# Switch.net
KiCad netlist of a schematic drawn in Altium Designer
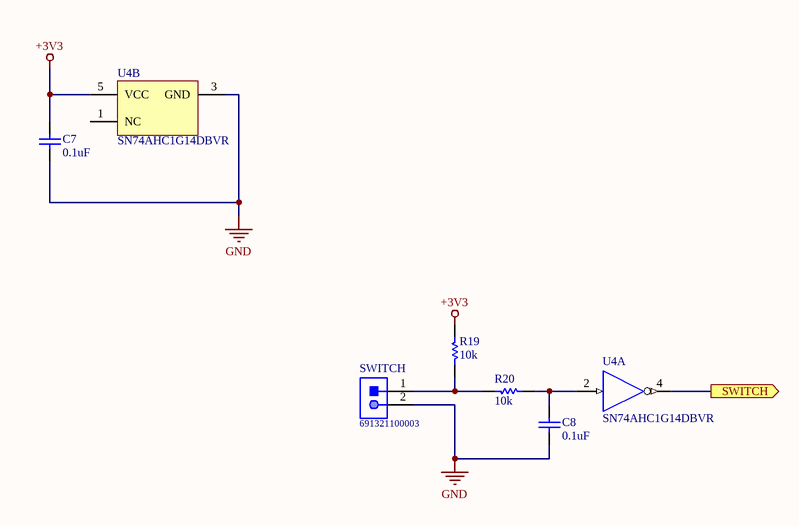
[diagram p0: Switch.SchDoc]

(export (version "E")
  (design (tool "Eeschema 10.0.6"))
  (components
    (comp (ref "C7")
      (value "0.1uF")
      (footprint "CAPC1608X87X35NL15T15")
      (fields (field (name "PART NUMBER") "C0603X104K5RACTU") (field (name "MANUFACTURER") "Kemet"))
      (libsource (lib "Altium Content Vault") (part "CAP"))
    )
    (comp (ref "C8")
      (value "0.1uF")
      (footprint "CAPC1608X87X35NL15T15")
      (fields (field (name "PART NUMBER") "C0603X104K5RACTU") (field (name "MANUFACTURER") "Kemet"))
      (libsource (lib "Altium Content Vault") (part "CAP"))
    )
    (comp (ref "R19")
      (value "10k")
      (footprint "RESC1609X55X30LL15T15")
      (description "Chip Resistor, 10 KOhm, +/- 1%, 0.1 W, -55 to 155 degC, 0603 (1608 Metric), RoHS, Tape and Reel")
      (fields (field (name "TOLERANCE") "1%") (field (name "MANUFACTURER") "Panasonic"))
      (libsource (lib "Altium Content Vault") (part "RES-2"))
    )
    (comp (ref "R20")
      (value "10k")
      (footprint "RESC1609X55X30LL15T15")
      (description "Chip Resistor, 10 KOhm, +/- 1%, 0.1 W, -55 to 155 degC, 0603 (1608 Metric), RoHS, Tape and Reel")
      (fields (field (name "TOLERANCE") "1%") (field (name "MANUFACTURER") "Panasonic"))
      (libsource (lib "Altium Content Vault") (part "RES-2"))
    )
    (comp (ref "SWITCH")
      (value "691321100003")
      (footprint "691321100002")
      (description "Serie 3211 - 3.50mm Vertical PCB Header WR-TBL, 2 pin")
      (fields
        (field (name "PART NUMBER") "691321100002")
        (field (name "MANUFACTURER") "Wurth Elektronik")
        (field (name "PUBLISHER") "WurthElektronik")
      )
      (libsource (lib "Altium Content Vault") (part "WE-CN-1P-M-R2"))
    )
    (comp (ref "U4")
      (value "SN74AHC1G14DBVR")
      (footprint "DBV0005A_L")
      (fields (field (name "MANUFACTURER") "Texas Instruments"))
      (libsource (lib "Altium Content Vault") (part "TI-SN74XXX1XX4-XX-5"))
    )
  )
  (nets
    (net (code "1") (name "+3V3") (class "Default")
      (node (ref "C7") (pin "1") (pinfunction "1_1") (pintype "passive"))
      (node (ref "R19") (pin "2") (pinfunction "2_2") (pintype "passive"))
      (node (ref "U4") (pin "5") (pinfunction "VCC_5") (pintype "power_in"))
    )
    (net (code "2") (name "/SWITCH") (class "Default")
      (node (ref "U4") (pin "4") (pinfunction "Y_4") (pintype "output"))
    )
    (net (code "3") (name "GND") (class "Default")
      (node (ref "C7") (pin "2") (pinfunction "2_2") (pintype "passive"))
      (node (ref "C8") (pin "2") (pinfunction "2_2") (pintype "passive"))
      (node (ref "SWITCH") (pin "2") (pinfunction "2_2") (pintype "passive"))
      (node (ref "U4") (pin "3") (pinfunction "GND_3") (pintype "power_in"))
    )
    (net (code "4") (name "Net-(R19-Pad1)") (class "Default")
      (node (ref "R19") (pin "1") (pinfunction "1_1") (pintype "passive"))
      (node (ref "R20") (pin "2") (pinfunction "2_2") (pintype "passive"))
      (node (ref "SWITCH") (pin "1") (pinfunction "1_1") (pintype "passive"))
    )
    (net (code "5") (name "Net-(U4A-A)") (class "Default")
      (node (ref "C8") (pin "1") (pinfunction "1_1") (pintype "passive"))
      (node (ref "R20") (pin "1") (pinfunction "1_1") (pintype "passive"))
      (node (ref "U4") (pin "2") (pinfunction "A_2") (pintype "input"))
    )
    (net (code "6") (name "unconnected-(U4B-NC-Pad1)") (class "Default")
      (node (ref "U4") (pin "1") (pinfunction "NC_1") (pintype "passive"))
    )
  )
)
